# Altimeter.net
KiCad netlist of a schematic drawn in Altium Designer
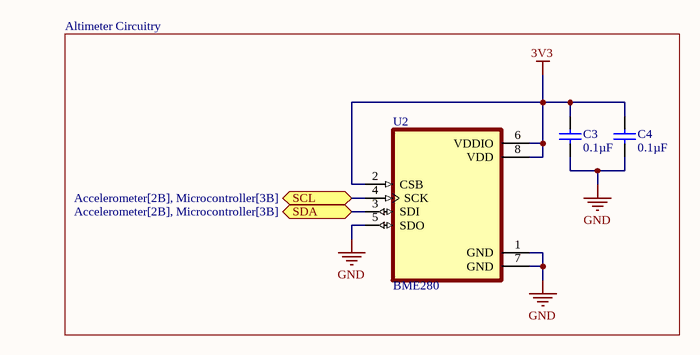
[diagram p0: Altimeter.SchDoc]

(export (version "E")
  (design (tool "Eeschema 10.0.6"))
  (components
    (comp (ref "C3")
      (value "0.1µF")
      (footprint "CAPC3216X100X50LL20T25")
      (description "Chip Capacitor, 100 nF, +/- 10%, 25 V, -55 to 125 degC, 1206 (3216 Metric), RoHS, Tape and Reel")
      (fields (field (name "MANUFACTURER") "Kemet"))
      (libsource (lib "Altium Content Vault") (part "CAP-NP-2"))
    )
    (comp (ref "C4")
      (value "0.1µF")
      (footprint "CAPC3216X100X50LL20T25")
      (description "Chip Capacitor, 100 nF, +/- 10%, 25 V, -55 to 125 degC, 1206 (3216 Metric), RoHS, Tape and Reel")
      (fields (field (name "MANUFACTURER") "Kemet"))
      (libsource (lib "Altium Content Vault") (part "CAP-NP-2"))
    )
    (comp (ref "U2")
      (value "BME280")
      (footprint "PSON65P250X250X100-8N")
      (libsource (lib "BME280") (part "BME280"))
    )
  )
  (nets
    (net (code "1") (name "/SCL") (class "Default")
      (node (ref "U2") (pin "4") (pinfunction "SCK_4") (pintype "input"))
    )
    (net (code "2") (name "/SDA") (class "Default")
      (node (ref "U2") (pin "3") (pinfunction "SDI_3") (pintype "bidirectional"))
    )
    (net (code "3") (name "3V3") (class "Default")
      (node (ref "C3") (pin "1") (pinfunction "1_1") (pintype "passive"))
      (node (ref "C4") (pin "1") (pinfunction "1_1") (pintype "passive"))
      (node (ref "U2") (pin "2") (pinfunction "CSB_2") (pintype "input"))
      (node (ref "U2") (pin "6") (pinfunction "VDDIO_6") (pintype "power_in"))
      (node (ref "U2") (pin "8") (pinfunction "VDD_8") (pintype "power_in"))
    )
    (net (code "4") (name "GND") (class "Default")
      (node (ref "C3") (pin "2") (pinfunction "2_2") (pintype "passive"))
      (node (ref "C4") (pin "2") (pinfunction "2_2") (pintype "passive"))
      (node (ref "U2") (pin "1") (pinfunction "GND_1") (pintype "power_in"))
      (node (ref "U2") (pin "5") (pinfunction "SDO_5") (pintype "bidirectional"))
      (node (ref "U2") (pin "7") (pinfunction "GND_7") (pintype "power_in"))
    )
  )
)
